# rcz80cpuv1.net
KiCad netlist of a schematic drawn in EAGLE
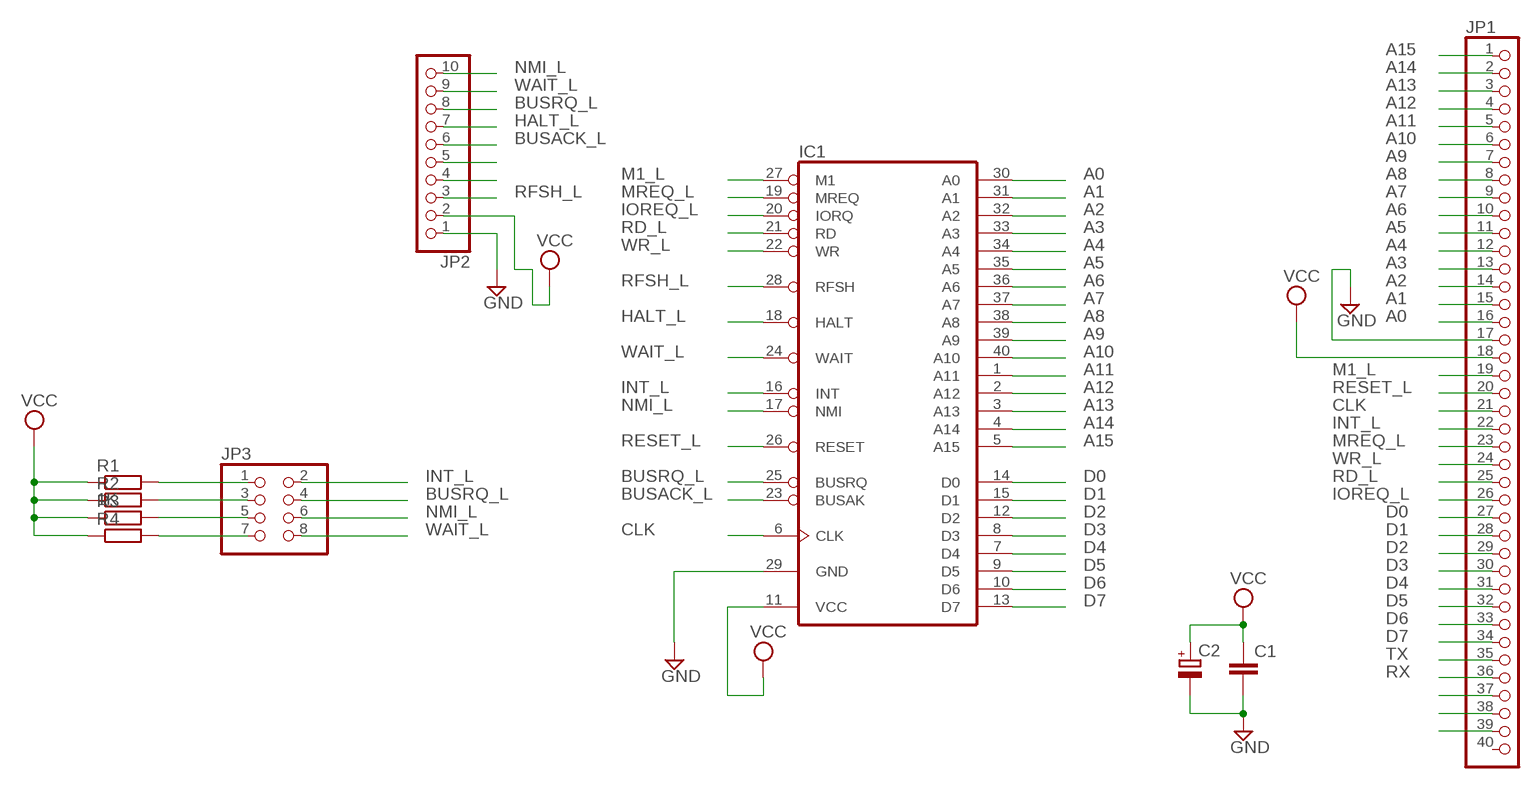
[diagram p0: schematic, sheet 1]

(export (version "E")
  (design (tool "Eeschema 10.0.6"))
  (components
    (comp (ref "C1")
      (value "C-EU025-024X044")
      (footprint "eagle-import:C025-024X044")
      (libsource (lib "eagle-import") (part "C-EU025-024X044"))
    )
    (comp (ref "C2")
      (value "CPOL-EUE2,5-6E")
      (footprint "eagle-import:E2,5-6E")
      (libsource (lib "eagle-import") (part "CPOL-EUE2,5-6E"))
    )
    (comp (ref "IC1")
      (value "Z80CPU")
      (footprint "eagle-import:DIL40")
      (libsource (lib "eagle-import") (part "Z80CPU"))
    )
    (comp (ref "JP1")
      (value "PINHD-1X40")
      (footprint "eagle-import:1X40")
      (libsource (lib "eagle-import") (part "PINHD-1X40"))
    )
    (comp (ref "JP2")
      (value "PINHD-1X10")
      (footprint "eagle-import:1X10")
      (libsource (lib "eagle-import") (part "PINHD-1X10"))
    )
    (comp (ref "JP3")
      (value "PINHD-2X4")
      (footprint "eagle-import:2X04")
      (libsource (lib "eagle-import") (part "PINHD-2X4"))
    )
    (comp (ref "R1")
      (value "1K")
      (footprint "eagle-import:0204_7")
      (libsource (lib "eagle-import") (part "R-EU_0204/7"))
    )
    (comp (ref "R2")
      (value "R-EU_0204/7")
      (footprint "eagle-import:0204_7")
      (libsource (lib "eagle-import") (part "R-EU_0204/7"))
    )
    (comp (ref "R3")
      (value "R-EU_0204/7")
      (footprint "eagle-import:0204_7")
      (libsource (lib "eagle-import") (part "R-EU_0204/7"))
    )
    (comp (ref "R4")
      (value "R-EU_0204/7")
      (footprint "eagle-import:0204_7")
      (libsource (lib "eagle-import") (part "R-EU_0204/7"))
    )
  )
  (nets
    (net (code "1") (name "/A0") (class "Default")
      (node (ref "IC1") (pin "30") (pinfunction "A0_30") (pintype "output"))
      (node (ref "JP1") (pin "16") (pinfunction "16_16") (pintype "passive"))
    )
    (net (code "2") (name "/A1") (class "Default")
      (node (ref "IC1") (pin "31") (pinfunction "A1_31") (pintype "output"))
      (node (ref "JP1") (pin "15") (pinfunction "15_15") (pintype "passive"))
    )
    (net (code "3") (name "/A2") (class "Default")
      (node (ref "IC1") (pin "32") (pinfunction "A2_32") (pintype "output"))
      (node (ref "JP1") (pin "14") (pinfunction "14_14") (pintype "passive"))
    )
    (net (code "4") (name "/A3") (class "Default")
      (node (ref "IC1") (pin "33") (pinfunction "A3_33") (pintype "output"))
      (node (ref "JP1") (pin "13") (pinfunction "13_13") (pintype "passive"))
    )
    (net (code "5") (name "/A4") (class "Default")
      (node (ref "IC1") (pin "34") (pinfunction "A4_34") (pintype "output"))
      (node (ref "JP1") (pin "12") (pinfunction "12_12") (pintype "passive"))
    )
    (net (code "6") (name "/A5") (class "Default")
      (node (ref "IC1") (pin "35") (pinfunction "A5_35") (pintype "output"))
      (node (ref "JP1") (pin "11") (pinfunction "11_11") (pintype "passive"))
    )
    (net (code "7") (name "/A6") (class "Default")
      (node (ref "IC1") (pin "36") (pinfunction "A6_36") (pintype "output"))
      (node (ref "JP1") (pin "10") (pinfunction "10_10") (pintype "passive"))
    )
    (net (code "8") (name "/A7") (class "Default")
      (node (ref "IC1") (pin "37") (pinfunction "A7_37") (pintype "output"))
      (node (ref "JP1") (pin "9") (pinfunction "9_9") (pintype "passive"))
    )
    (net (code "9") (name "/A8") (class "Default")
      (node (ref "IC1") (pin "38") (pinfunction "A8_38") (pintype "output"))
      (node (ref "JP1") (pin "8") (pinfunction "8_8") (pintype "passive"))
    )
    (net (code "10") (name "/A9") (class "Default")
      (node (ref "IC1") (pin "39") (pinfunction "A9_39") (pintype "output"))
      (node (ref "JP1") (pin "7") (pinfunction "7_7") (pintype "passive"))
    )
    (net (code "11") (name "/A10") (class "Default")
      (node (ref "IC1") (pin "40") (pinfunction "A10_40") (pintype "output"))
      (node (ref "JP1") (pin "6") (pinfunction "6_6") (pintype "passive"))
    )
    (net (code "12") (name "/A11") (class "Default")
      (node (ref "IC1") (pin "1") (pinfunction "A11_1") (pintype "output"))
      (node (ref "JP1") (pin "5") (pinfunction "5_5") (pintype "passive"))
    )
    (net (code "13") (name "/A12") (class "Default")
      (node (ref "IC1") (pin "2") (pinfunction "A12_2") (pintype "output"))
      (node (ref "JP1") (pin "4") (pinfunction "4_4") (pintype "passive"))
    )
    (net (code "14") (name "/A13") (class "Default")
      (node (ref "IC1") (pin "3") (pinfunction "A13_3") (pintype "output"))
      (node (ref "JP1") (pin "3") (pinfunction "3_3") (pintype "passive"))
    )
    (net (code "15") (name "/A14") (class "Default")
      (node (ref "IC1") (pin "4") (pinfunction "A14_4") (pintype "output"))
      (node (ref "JP1") (pin "2") (pinfunction "2_2") (pintype "passive"))
    )
    (net (code "16") (name "/A15") (class "Default")
      (node (ref "IC1") (pin "5") (pinfunction "A15_5") (pintype "output"))
      (node (ref "JP1") (pin "1") (pinfunction "1_1") (pintype "passive"))
    )
    (net (code "17") (name "/BUSACK_L") (class "Default")
      (node (ref "IC1") (pin "23") (pinfunction "BUSAK_23") (pintype "output"))
      (node (ref "JP2") (pin "6") (pinfunction "6_6") (pintype "passive"))
    )
    (net (code "18") (name "/BUSRQ_L") (class "Default")
      (node (ref "IC1") (pin "25") (pinfunction "BUSRQ_25") (pintype "input"))
      (node (ref "JP2") (pin "8") (pinfunction "8_8") (pintype "passive"))
      (node (ref "JP3") (pin "4") (pinfunction "4_4") (pintype "passive"))
    )
    (net (code "19") (name "/CLK") (class "Default")
      (node (ref "IC1") (pin "6") (pinfunction "CLK_6") (pintype "input"))
      (node (ref "JP1") (pin "21") (pinfunction "21_21") (pintype "passive"))
    )
    (net (code "20") (name "/D0") (class "Default")
      (node (ref "IC1") (pin "14") (pinfunction "D0_14") (pintype "bidirectional"))
      (node (ref "JP1") (pin "27") (pinfunction "27_27") (pintype "passive"))
    )
    (net (code "21") (name "/D1") (class "Default")
      (node (ref "IC1") (pin "15") (pinfunction "D1_15") (pintype "bidirectional"))
      (node (ref "JP1") (pin "28") (pinfunction "28_28") (pintype "passive"))
    )
    (net (code "22") (name "/D2") (class "Default")
      (node (ref "IC1") (pin "12") (pinfunction "D2_12") (pintype "bidirectional"))
      (node (ref "JP1") (pin "29") (pinfunction "29_29") (pintype "passive"))
    )
    (net (code "23") (name "/D3") (class "Default")
      (node (ref "IC1") (pin "8") (pinfunction "D3_8") (pintype "bidirectional"))
      (node (ref "JP1") (pin "30") (pinfunction "30_30") (pintype "passive"))
    )
    (net (code "24") (name "/D4") (class "Default")
      (node (ref "IC1") (pin "7") (pinfunction "D4_7") (pintype "bidirectional"))
      (node (ref "JP1") (pin "31") (pinfunction "31_31") (pintype "passive"))
    )
    (net (code "25") (name "/D5") (class "Default")
      (node (ref "IC1") (pin "9") (pinfunction "D5_9") (pintype "bidirectional"))
      (node (ref "JP1") (pin "32") (pinfunction "32_32") (pintype "passive"))
    )
    (net (code "26") (name "/D6") (class "Default")
      (node (ref "IC1") (pin "10") (pinfunction "D6_10") (pintype "bidirectional"))
      (node (ref "JP1") (pin "33") (pinfunction "33_33") (pintype "passive"))
    )
    (net (code "27") (name "/D7") (class "Default")
      (node (ref "IC1") (pin "13") (pinfunction "D7_13") (pintype "bidirectional"))
      (node (ref "JP1") (pin "34") (pinfunction "34_34") (pintype "passive"))
    )
    (net (code "28") (name "/HALT_L") (class "Default")
      (node (ref "IC1") (pin "18") (pinfunction "HALT_18") (pintype "output"))
      (node (ref "JP2") (pin "7") (pinfunction "7_7") (pintype "passive"))
    )
    (net (code "29") (name "/INT_L") (class "Default")
      (node (ref "IC1") (pin "16") (pinfunction "INT_16") (pintype "input"))
      (node (ref "JP1") (pin "22") (pinfunction "22_22") (pintype "passive"))
      (node (ref "JP3") (pin "2") (pinfunction "2_2") (pintype "passive"))
    )
    (net (code "30") (name "/IOREQ_L") (class "Default")
      (node (ref "IC1") (pin "20") (pinfunction "IORQ_20") (pintype "output"))
      (node (ref "JP1") (pin "26") (pinfunction "26_26") (pintype "passive"))
    )
    (net (code "31") (name "/M1_L") (class "Default")
      (node (ref "IC1") (pin "27") (pinfunction "M1_27") (pintype "output"))
      (node (ref "JP1") (pin "19") (pinfunction "19_19") (pintype "passive"))
    )
    (net (code "32") (name "/MREQ_L") (class "Default")
      (node (ref "IC1") (pin "19") (pinfunction "MREQ_19") (pintype "output"))
      (node (ref "JP1") (pin "23") (pinfunction "23_23") (pintype "passive"))
    )
    (net (code "33") (name "/NMI_L") (class "Default")
      (node (ref "IC1") (pin "17") (pinfunction "NMI_17") (pintype "input"))
      (node (ref "JP2") (pin "10") (pinfunction "10_10") (pintype "passive"))
      (node (ref "JP3") (pin "6") (pinfunction "6_6") (pintype "passive"))
    )
    (net (code "34") (name "/RD_L") (class "Default")
      (node (ref "IC1") (pin "21") (pinfunction "RD_21") (pintype "output"))
      (node (ref "JP1") (pin "25") (pinfunction "25_25") (pintype "passive"))
    )
    (net (code "35") (name "/RESET_L") (class "Default")
      (node (ref "IC1") (pin "26") (pinfunction "RESET_26") (pintype "input"))
      (node (ref "JP1") (pin "20") (pinfunction "20_20") (pintype "passive"))
    )
    (net (code "36") (name "/RFSH_L") (class "Default")
      (node (ref "IC1") (pin "28") (pinfunction "RFSH_28") (pintype "output"))
      (node (ref "JP2") (pin "3") (pinfunction "3_3") (pintype "passive"))
    )
    (net (code "37") (name "/RX") (class "Default")
      (node (ref "JP1") (pin "36") (pinfunction "36_36") (pintype "passive"))
    )
    (net (code "38") (name "/TX") (class "Default")
      (node (ref "JP1") (pin "35") (pinfunction "35_35") (pintype "passive"))
    )
    (net (code "39") (name "/WAIT_L") (class "Default")
      (node (ref "IC1") (pin "24") (pinfunction "WAIT_24") (pintype "input"))
      (node (ref "JP2") (pin "9") (pinfunction "9_9") (pintype "passive"))
      (node (ref "JP3") (pin "8") (pinfunction "8_8") (pintype "passive"))
    )
    (net (code "40") (name "/WR_L") (class "Default")
      (node (ref "IC1") (pin "22") (pinfunction "WR_22") (pintype "output"))
      (node (ref "JP1") (pin "24") (pinfunction "24_24") (pintype "passive"))
    )
    (net (code "41") (name "GND") (class "Default")
      (node (ref "C1") (pin "2") (pinfunction "2_2") (pintype "passive"))
      (node (ref "C2") (pin "-") (pinfunction "-_-") (pintype "passive"))
      (node (ref "IC1") (pin "29") (pinfunction "GND_29") (pintype "power_in"))
      (node (ref "JP1") (pin "17") (pinfunction "17_17") (pintype "passive"))
      (node (ref "JP2") (pin "1") (pinfunction "1_1") (pintype "passive"))
    )
    (net (code "42") (name "Net-(JP3-Pad1)") (class "Default")
      (node (ref "JP3") (pin "1") (pinfunction "1_1") (pintype "passive"))
      (node (ref "R1") (pin "2") (pinfunction "2_2") (pintype "passive"))
    )
    (net (code "43") (name "Net-(JP3-Pad3)") (class "Default")
      (node (ref "JP3") (pin "3") (pinfunction "3_3") (pintype "passive"))
      (node (ref "R2") (pin "2") (pinfunction "2_2") (pintype "passive"))
    )
    (net (code "44") (name "Net-(JP3-Pad5)") (class "Default")
      (node (ref "JP3") (pin "5") (pinfunction "5_5") (pintype "passive"))
      (node (ref "R3") (pin "2") (pinfunction "2_2") (pintype "passive"))
    )
    (net (code "45") (name "Net-(JP3-Pad7)") (class "Default")
      (node (ref "JP3") (pin "7") (pinfunction "7_7") (pintype "passive"))
      (node (ref "R4") (pin "2") (pinfunction "2_2") (pintype "passive"))
    )
    (net (code "46") (name "VCC") (class "Default")
      (node (ref "C1") (pin "1") (pinfunction "1_1") (pintype "passive"))
      (node (ref "C2") (pin "+") (pinfunction "+_+") (pintype "passive"))
      (node (ref "IC1") (pin "11") (pinfunction "VCC_11") (pintype "power_in"))
      (node (ref "JP1") (pin "18") (pinfunction "18_18") (pintype "passive"))
      (node (ref "JP2") (pin "2") (pinfunction "2_2") (pintype "passive"))
      (node (ref "R1") (pin "1") (pinfunction "1_1") (pintype "passive"))
      (node (ref "R2") (pin "1") (pinfunction "1_1") (pintype "passive"))
      (node (ref "R3") (pin "1") (pinfunction "1_1") (pintype "passive"))
      (node (ref "R4") (pin "1") (pinfunction "1_1") (pintype "passive"))
    )
    (net (code "47") (name "unconnected-(JP1-Pad37)") (class "Default")
      (node (ref "JP1") (pin "37") (pinfunction "37_37") (pintype "passive"))
    )
    (net (code "48") (name "unconnected-(JP1-Pad38)") (class "Default")
      (node (ref "JP1") (pin "38") (pinfunction "38_38") (pintype "passive"))
    )
    (net (code "49") (name "unconnected-(JP1-Pad39)") (class "Default")
      (node (ref "JP1") (pin "39") (pinfunction "39_39") (pintype "passive"))
    )
    (net (code "50") (name "unconnected-(JP1-Pad40)") (class "Default")
      (node (ref "JP1") (pin "40") (pinfunction "40_40") (pintype "passive"))
    )
    (net (code "51") (name "unconnected-(JP2-Pad4)") (class "Default")
      (node (ref "JP2") (pin "4") (pinfunction "4_4") (pintype "passive"))
    )
    (net (code "52") (name "unconnected-(JP2-Pad5)") (class "Default")
      (node (ref "JP2") (pin "5") (pinfunction "5_5") (pintype "passive"))
    )
  )
)
